# CPU_LPC1776_2.net
KiCad netlist of a schematic drawn in Altium Designer
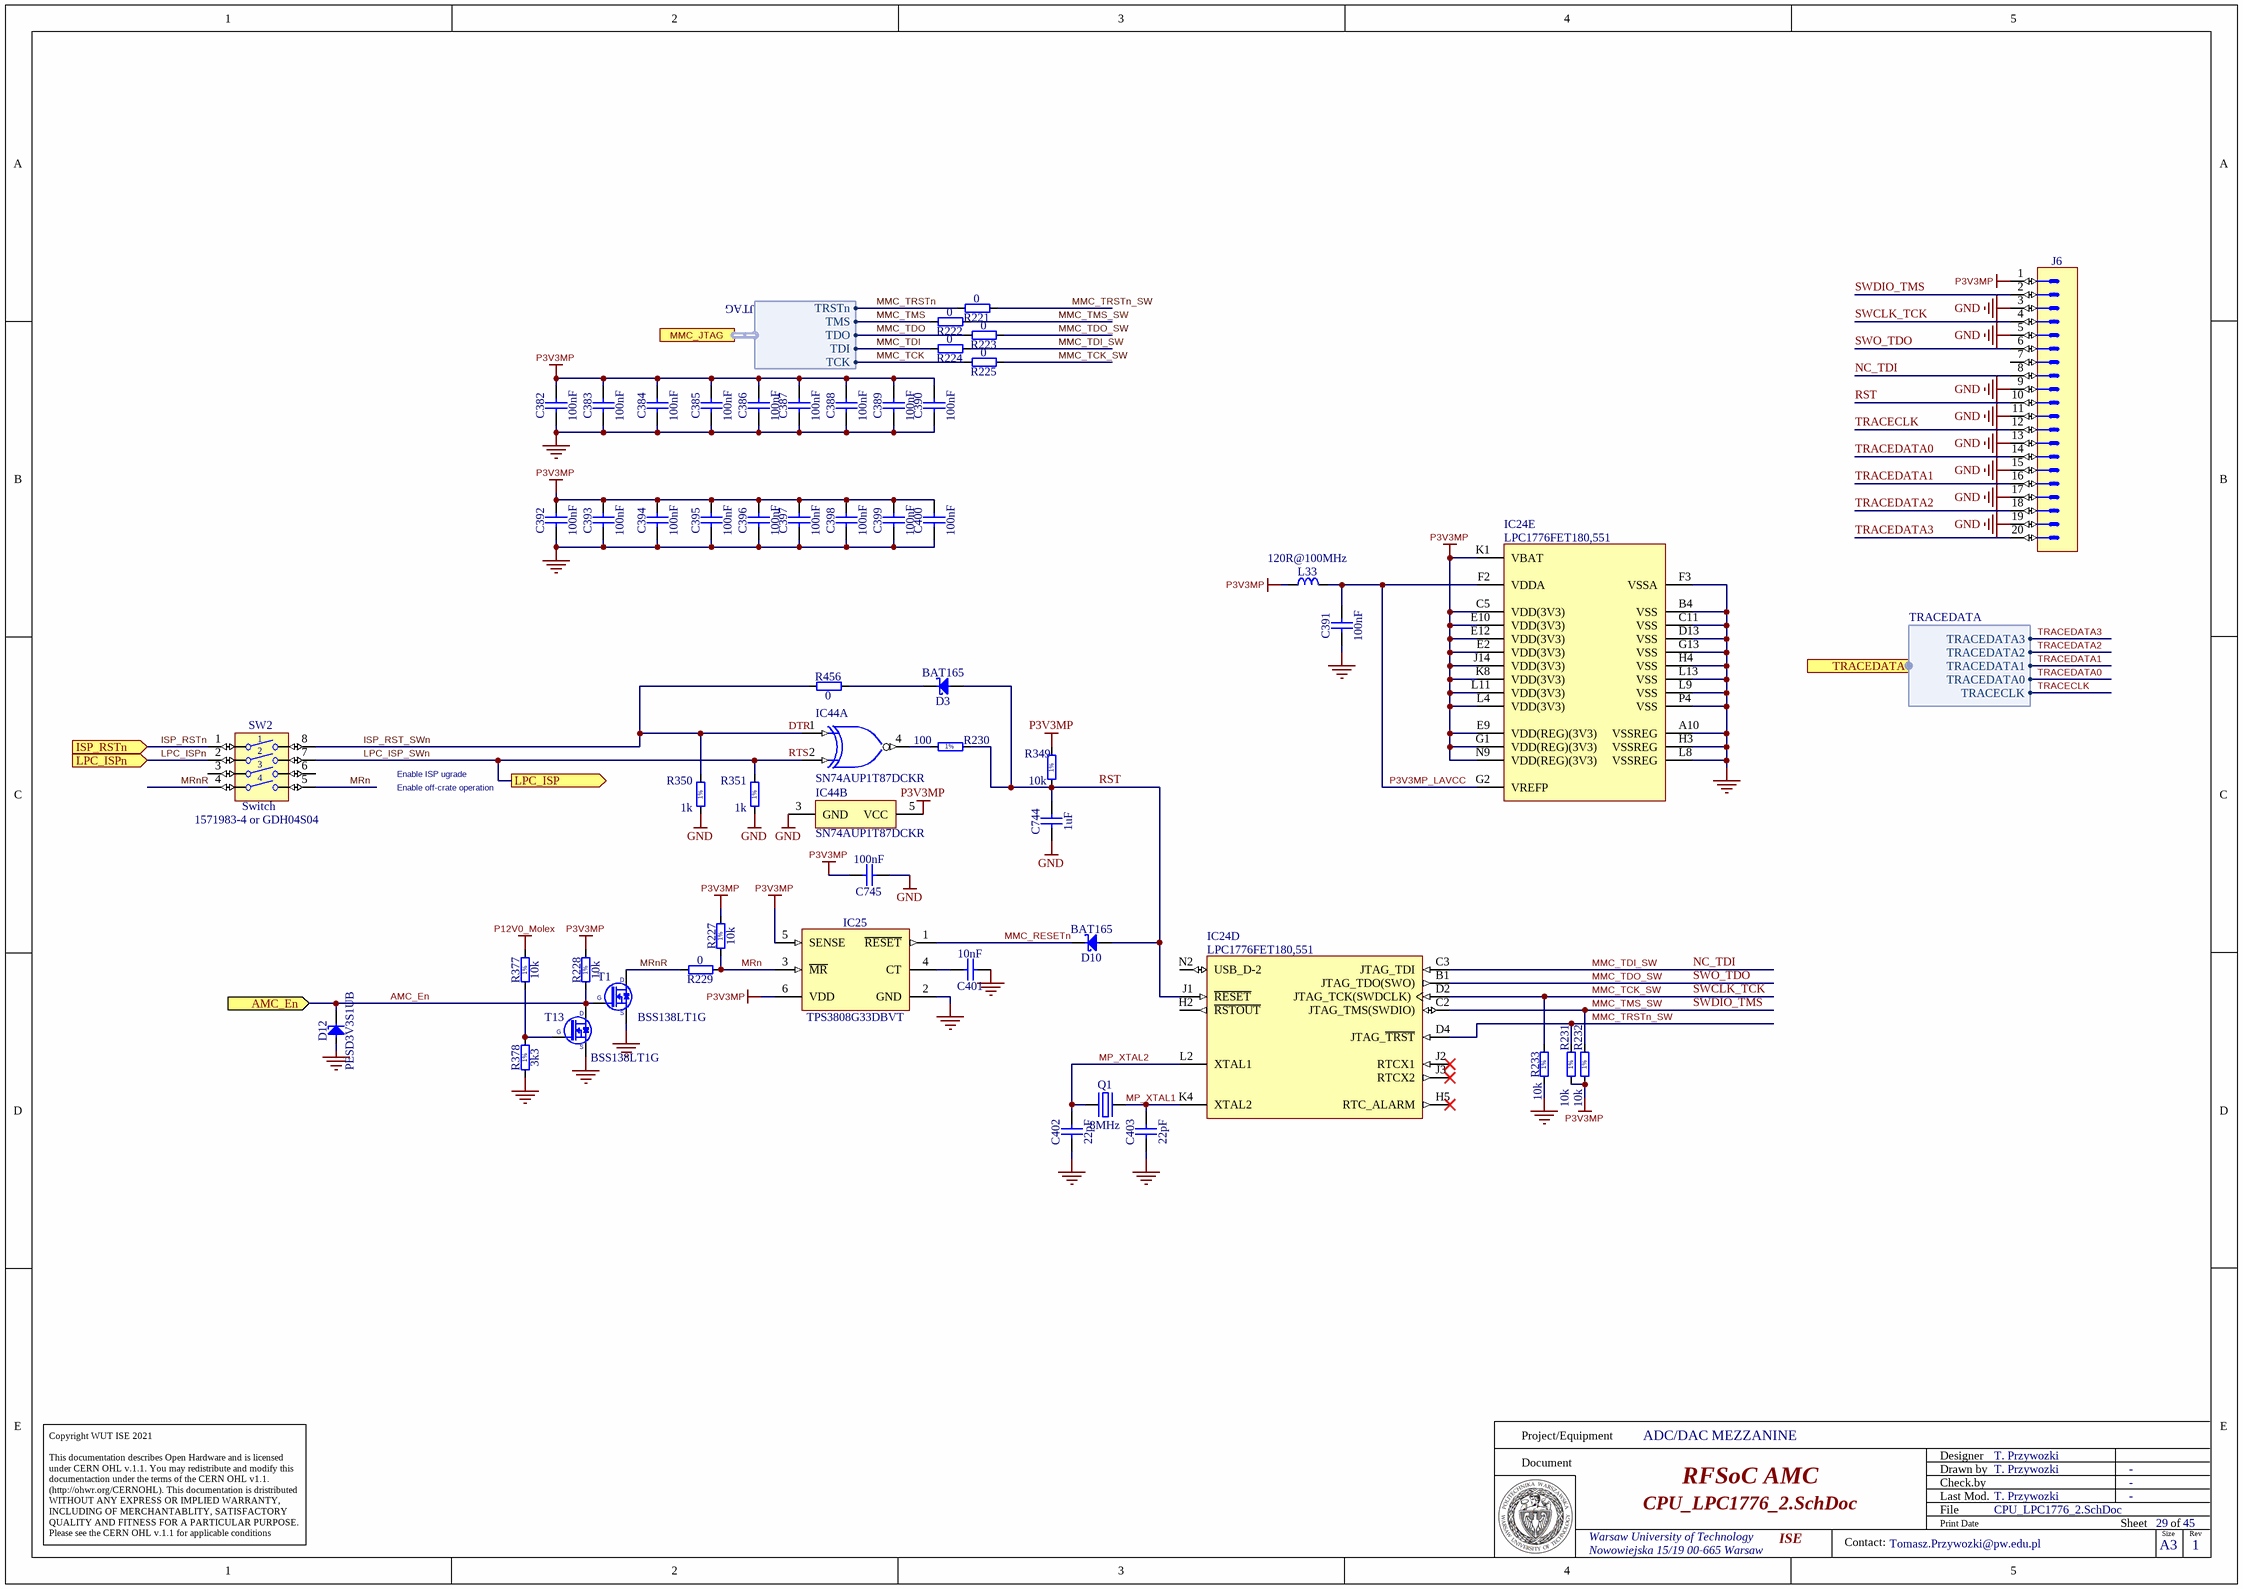
[diagram p0: CPU_LPC1776_2.SchDoc]

(export (version "E")
  (design (tool "Eeschema 10.0.6"))
  (components
    (comp (ref "C382")
      (value "100nF")
      (footprint "CAPC0603X33N")
      (description "Non-polarised capacitor")
      (fields
        (field (name "MANUFACTURER PART NUMBER") "CC0201_100NF_6.3V_10%_X5R")
        (field (name "MANUFACTURER") "GENERIC")
        (field (name "AUTHOR") "CERN DEM JLC")
      )
      (libsource (lib "Capacitors") (part "Capacitor - non polarized"))
    )
    (comp (ref "C383")
      (value "100nF")
      (footprint "CAPC0603X33N")
      (description "Non-polarised capacitor")
      (fields
        (field (name "MANUFACTURER PART NUMBER") "CC0201_100NF_6.3V_10%_X5R")
        (field (name "MANUFACTURER") "GENERIC")
        (field (name "AUTHOR") "CERN DEM JLC")
      )
      (libsource (lib "Capacitors") (part "Capacitor - non polarized"))
    )
    (comp (ref "C384")
      (value "100nF")
      (footprint "CAPC0603X33N")
      (description "Non-polarised capacitor")
      (fields
        (field (name "MANUFACTURER PART NUMBER") "CC0201_100NF_6.3V_10%_X5R")
        (field (name "MANUFACTURER") "GENERIC")
        (field (name "AUTHOR") "CERN DEM JLC")
      )
      (libsource (lib "Capacitors") (part "Capacitor - non polarized"))
    )
    (comp (ref "C385")
      (value "100nF")
      (footprint "CAPC0603X33N")
      (description "Non-polarised capacitor")
      (fields
        (field (name "MANUFACTURER PART NUMBER") "CC0201_100NF_6.3V_10%_X5R")
        (field (name "MANUFACTURER") "GENERIC")
        (field (name "AUTHOR") "CERN DEM JLC")
      )
      (libsource (lib "Capacitors") (part "Capacitor - non polarized"))
    )
    (comp (ref "C386")
      (value "100nF")
      (footprint "CAPC0603X33N")
      (description "Non-polarised capacitor")
      (fields
        (field (name "MANUFACTURER PART NUMBER") "CC0201_100NF_6.3V_10%_X5R")
        (field (name "MANUFACTURER") "GENERIC")
        (field (name "AUTHOR") "CERN DEM JLC")
      )
      (libsource (lib "Capacitors") (part "Capacitor - non polarized"))
    )
    (comp (ref "C387")
      (value "100nF")
      (footprint "CAPC0603X33N")
      (description "Non-polarised capacitor")
      (fields
        (field (name "MANUFACTURER PART NUMBER") "CC0201_100NF_6.3V_10%_X5R")
        (field (name "MANUFACTURER") "GENERIC")
        (field (name "AUTHOR") "CERN DEM JLC")
      )
      (libsource (lib "Capacitors") (part "Capacitor - non polarized"))
    )
    (comp (ref "C388")
      (value "100nF")
      (footprint "CAPC0603X33N")
      (description "Non-polarised capacitor")
      (fields
        (field (name "MANUFACTURER PART NUMBER") "CC0201_100NF_6.3V_10%_X5R")
        (field (name "MANUFACTURER") "GENERIC")
        (field (name "AUTHOR") "CERN DEM JLC")
      )
      (libsource (lib "Capacitors") (part "Capacitor - non polarized"))
    )
    (comp (ref "C389")
      (value "100nF")
      (footprint "CAPC0603X33N")
      (description "Non-polarised capacitor")
      (fields
        (field (name "MANUFACTURER PART NUMBER") "CC0201_100NF_6.3V_10%_X5R")
        (field (name "MANUFACTURER") "GENERIC")
        (field (name "AUTHOR") "CERN DEM JLC")
      )
      (libsource (lib "Capacitors") (part "Capacitor - non polarized"))
    )
    (comp (ref "C390")
      (value "100nF")
      (footprint "CAPC0603X33N")
      (description "Non-polarised capacitor")
      (fields
        (field (name "MANUFACTURER PART NUMBER") "CC0201_100NF_6.3V_10%_X5R")
        (field (name "MANUFACTURER") "GENERIC")
        (field (name "AUTHOR") "CERN DEM JLC")
      )
      (libsource (lib "Capacitors") (part "Capacitor - non polarized"))
    )
    (comp (ref "C391")
      (value "100nF")
      (footprint "CAPC0603X33N")
      (description "Non-polarised capacitor")
      (fields
        (field (name "MANUFACTURER PART NUMBER") "CC0201_100NF_6.3V_10%_X5R")
        (field (name "MANUFACTURER") "GENERIC")
        (field (name "AUTHOR") "CERN DEM JLC")
      )
      (libsource (lib "Capacitors") (part "Capacitor - non polarized"))
    )
    (comp (ref "C392")
      (value "100nF")
      (footprint "CAPC0603X33N")
      (description "Non-polarised capacitor")
      (fields
        (field (name "MANUFACTURER PART NUMBER") "CC0201_100NF_6.3V_10%_X5R")
        (field (name "MANUFACTURER") "GENERIC")
        (field (name "AUTHOR") "CERN DEM JLC")
      )
      (libsource (lib "Capacitors") (part "Capacitor - non polarized"))
    )
    (comp (ref "C393")
      (value "100nF")
      (footprint "CAPC0603X33N")
      (description "Non-polarised capacitor")
      (fields
        (field (name "MANUFACTURER PART NUMBER") "CC0201_100NF_6.3V_10%_X5R")
        (field (name "MANUFACTURER") "GENERIC")
        (field (name "AUTHOR") "CERN DEM JLC")
      )
      (libsource (lib "Capacitors") (part "Capacitor - non polarized"))
    )
    (comp (ref "C394")
      (value "100nF")
      (footprint "CAPC0603X33N")
      (description "Non-polarised capacitor")
      (fields
        (field (name "MANUFACTURER PART NUMBER") "CC0201_100NF_6.3V_10%_X5R")
        (field (name "MANUFACTURER") "GENERIC")
        (field (name "AUTHOR") "CERN DEM JLC")
      )
      (libsource (lib "Capacitors") (part "Capacitor - non polarized"))
    )
    (comp (ref "C395")
      (value "100nF")
      (footprint "CAPC0603X33N")
      (description "Non-polarised capacitor")
      (fields
        (field (name "MANUFACTURER PART NUMBER") "CC0201_100NF_6.3V_10%_X5R")
        (field (name "MANUFACTURER") "GENERIC")
        (field (name "AUTHOR") "CERN DEM JLC")
      )
      (libsource (lib "Capacitors") (part "Capacitor - non polarized"))
    )
    (comp (ref "C396")
      (value "100nF")
      (footprint "CAPC0603X33N")
      (description "Non-polarised capacitor")
      (fields
        (field (name "MANUFACTURER PART NUMBER") "CC0201_100NF_6.3V_10%_X5R")
        (field (name "MANUFACTURER") "GENERIC")
        (field (name "AUTHOR") "CERN DEM JLC")
      )
      (libsource (lib "Capacitors") (part "Capacitor - non polarized"))
    )
    (comp (ref "C397")
      (value "100nF")
      (footprint "CAPC0603X33N")
      (description "Non-polarised capacitor")
      (fields
        (field (name "MANUFACTURER PART NUMBER") "CC0201_100NF_6.3V_10%_X5R")
        (field (name "MANUFACTURER") "GENERIC")
        (field (name "AUTHOR") "CERN DEM JLC")
      )
      (libsource (lib "Capacitors") (part "Capacitor - non polarized"))
    )
    (comp (ref "C398")
      (value "100nF")
      (footprint "CAPC0603X33N")
      (description "Non-polarised capacitor")
      (fields
        (field (name "MANUFACTURER PART NUMBER") "CC0201_100NF_6.3V_10%_X5R")
        (field (name "MANUFACTURER") "GENERIC")
        (field (name "AUTHOR") "CERN DEM JLC")
      )
      (libsource (lib "Capacitors") (part "Capacitor - non polarized"))
    )
    (comp (ref "C399")
      (value "100nF")
      (footprint "CAPC0603X33N")
      (description "Non-polarised capacitor")
      (fields
        (field (name "MANUFACTURER PART NUMBER") "CC0201_100NF_6.3V_10%_X5R")
        (field (name "MANUFACTURER") "GENERIC")
        (field (name "AUTHOR") "CERN DEM JLC")
      )
      (libsource (lib "Capacitors") (part "Capacitor - non polarized"))
    )
    (comp (ref "C400")
      (value "100nF")
      (footprint "CAPC0603X33N")
      (description "Non-polarised capacitor")
      (fields
        (field (name "MANUFACTURER PART NUMBER") "CC0201_100NF_6.3V_10%_X5R")
        (field (name "MANUFACTURER") "GENERIC")
        (field (name "AUTHOR") "CERN DEM JLC")
      )
      (libsource (lib "Capacitors") (part "Capacitor - non polarized"))
    )
    (comp (ref "C401")
      (value "10nF")
      (footprint "CAPC1005X55N")
      (description "Non-polarised capacitor")
      (fields
        (field (name "MANUFACTURER PART NUMBER") "CC0402_10NF_16V_10%_X7R")
        (field (name "MANUFACTURER") "GENERIC")
        (field (name "AUTHOR") "CERN DEM JLC")
      )
      (libsource (lib "Capacitors") (part "Capacitor - non polarized"))
    )
    (comp (ref "C402")
      (value "22pF")
      (footprint "CAPC1005X55N")
      (description "Non-polarised capacitor")
      (fields
        (field (name "MANUFACTURER PART NUMBER") "CC0402_22PF_50V_5%_C0G")
        (field (name "MANUFACTURER") "GENERIC")
        (field (name "AUTHOR") "CERN DEM JLC")
      )
      (libsource (lib "Capacitors") (part "Capacitor - non polarized"))
    )
    (comp (ref "C403")
      (value "22pF")
      (footprint "CAPC1005X55N")
      (description "Non-polarised capacitor")
      (fields
        (field (name "MANUFACTURER PART NUMBER") "CC0402_22PF_50V_5%_C0G")
        (field (name "MANUFACTURER") "GENERIC")
        (field (name "AUTHOR") "CERN DEM JLC")
      )
      (libsource (lib "Capacitors") (part "Capacitor - non polarized"))
    )
    (comp (ref "C744")
      (value "1uF")
      (footprint "CAPC1608X87N")
      (description "Non-polarised capacitor")
      (fields
        (field (name "PART NUMBER") "CC0603_1UF_16V_10%_X7R")
        (field (name "VOLTAGE") "16V")
        (field (name "AUTHOR") "CERN DEM JLC")
      )
      (libsource (lib "Capacitors") (part "Capacitor - non polarized"))
    )
    (comp (ref "C745")
      (value "100nF")
      (footprint "CAPC0603X33N")
      (description "Non-polarised capacitor")
      (fields
        (field (name "PART NUMBER") "CC0201_100NF_6.3V_10%_X5R")
        (field (name "VOLTAGE") "6.3V")
        (field (name "AUTHOR") "CERN DEM JLC")
      )
      (libsource (lib "Capacitors") (part "Capacitor - non polarized"))
    )
    (comp (ref "D3")
      (value "BAT165")
      (footprint "SOD2512X110N")
      (description "Schottky Diode")
      (fields
        (field (name "MANUFACTURER") "INFINEON")
        (field (name "VOLTAGE") "40V")
        (field (name "AUTHOR") "CERN DEM JLC")
      )
      (libsource (lib "ICs And Semiconductors") (part "Diode Schottky"))
    )
    (comp (ref "D10")
      (value "BAT165")
      (footprint "SOD2512X110N")
      (description "Schottky Diode")
      (fields
        (field (name "MANUFACTURER") "INFINEON")
        (field (name "VOLTAGE") "40V")
        (field (name "AUTHOR") "CERN DEM JLC")
      )
      (libsource (lib "ICs And Semiconductors") (part "Diode Schottky"))
    )
    (comp (ref "D12")
      (value "PESD3V3S1UB")
      (footprint "SODFL1608X65N")
      (description "ESD protection diode")
      (fields
        (field (name "MANUFACTURER") "NXP SEMICONDUCTORS")
        (field (name "VOLTAGE") "3V3")
        (field (name "AUTHOR") "CERN DEM JLC")
      )
      (libsource (lib "ICs And Semiconductors") (part "Diode ESD"))
    )
    (comp (ref "IC24")
      (value "LPC1776FET180,551")
      (footprint "BGA180C80P14X14_1200X1200X120")
      (fields (field (name "MANUFACTURER") "NXP SEMICONDUCTORS") (field (name "AUTHOR") "CERN DEM JMW"))
      (libsource (lib "ICs And Semiconductors") (part "LPC1776FET180,551"))
    )
    (comp (ref "IC25")
      (value "TPS3808G33DBVT")
      (footprint "SOT95P280X145-6N")
      (description "Low Quiescent Current, Programmable-Delay Supervisory Circuit")
      (fields (field (name "MANUFACTURER") "TEXAS INSTRUMENTS") (field (name "AUTHOR") "CERN DEM JLC"))
      (libsource (lib "ICs And Semiconductors") (part "TPS3808xxxDBV"))
    )
    (comp (ref "IC44")
      (value "SN74AUP1T87DCKR")
      (footprint "DCK0005A_L")
      (fields
        (field (name "GENERIC PART NUMBER") "SN74AUP1T87")
        (field (name "MANUFACTURER") "Texas Instruments")
      )
      (libsource (lib "") (part "TI-SN74AUP1T87-DCK0005A-5_1"))
    )
    (comp (ref "J6")
      (value "Header 20")
      (footprint "SAMTEC_FTSH-110-01-F-DV-K")
      (description "Connector 20 Male")
      (fields
        (field (name "PART NUMBER") "SAMTEC_FTSH-110-01-F-DV-K")
        (field (name "MANUFACTURER") "SAMTEC")
        (field (name "AUTHOR") "CERN DEM JLC")
      )
      (libsource (lib "Connectors") (part "Connector 20 Male"))
    )
    (comp (ref "L33")
      (value "120R@100MHz")
      (footprint "INDC1608X95N")
      (description "Inductor")
      (fields
        (field (name "MANUFACTURER PART NUMBER") "BLM18PG121SN1D")
        (field (name "MANUFACTURER") "MURATA")
        (field (name "AUTHOR") "CERN DEM BC")
      )
      (libsource (lib "Inductors & Transformers") (part "Inductor"))
    )
    (comp (ref "Q1")
      (value "8MHz")
      (footprint "XTAL_TXC_7A")
      (description "Quartz Crystal")
      (fields
        (field (name "MANUFACTURER PART NUMBER") "7A-8.000MAAE-T")
        (field (name "MANUFACTURER") "TXC CORPORATION")
        (field (name "AUTHOR") "CERN DEM JLC")
      )
      (libsource (lib "ICs And Semiconductors") (part "Quartz Crystal"))
    )
    (comp (ref "R221")
      (value "0")
      (footprint "RESC1005X40N")
      (description "Resistor")
      (fields
        (field (name "MANUFACTURER PART NUMBER") "R0402_0R_JUMPER")
        (field (name "MANUFACTURER") "GENERIC")
        (field (name "AUTHOR") "CERN DEM JLC")
      )
      (libsource (lib "Resistors") (part "Resistor"))
    )
    (comp (ref "R222")
      (value "0")
      (footprint "RESC1005X40N")
      (description "Resistor")
      (fields
        (field (name "MANUFACTURER PART NUMBER") "R0402_0R_JUMPER")
        (field (name "MANUFACTURER") "GENERIC")
        (field (name "AUTHOR") "CERN DEM JLC")
      )
      (libsource (lib "Resistors") (part "Resistor"))
    )
    (comp (ref "R223")
      (value "0")
      (footprint "RESC1005X40N")
      (description "Resistor")
      (fields
        (field (name "MANUFACTURER PART NUMBER") "R0402_0R_JUMPER")
        (field (name "MANUFACTURER") "GENERIC")
        (field (name "AUTHOR") "CERN DEM JLC")
      )
      (libsource (lib "Resistors") (part "Resistor"))
    )
    (comp (ref "R224")
      (value "0")
      (footprint "RESC1005X40N")
      (description "Resistor")
      (fields
        (field (name "MANUFACTURER PART NUMBER") "R0402_0R_JUMPER")
        (field (name "MANUFACTURER") "GENERIC")
        (field (name "AUTHOR") "CERN DEM JLC")
      )
      (libsource (lib "Resistors") (part "Resistor"))
    )
    (comp (ref "R225")
      (value "0")
      (footprint "RESC1005X40N")
      (description "Resistor")
      (fields
        (field (name "MANUFACTURER PART NUMBER") "R0402_0R_JUMPER")
        (field (name "MANUFACTURER") "GENERIC")
        (field (name "AUTHOR") "CERN DEM JLC")
      )
      (libsource (lib "Resistors") (part "Resistor"))
    )
    (comp (ref "R227")
      (value "10k")
      (footprint "RESC1005X40N")
      (description "Resistor - 1%")
      (fields
        (field (name "MANUFACTURER PART NUMBER") "R0402_10K_1%_0.0625W_100PPM")
        (field (name "MANUFACTURER") "GENERIC")
        (field (name "AUTHOR") "CERN DEM JLC")
      )
      (libsource (lib "Resistors") (part "Resistor - 1%"))
    )
    (comp (ref "R228")
      (value "10k")
      (footprint "RESC1005X40N")
      (description "Resistor - 1%")
      (fields
        (field (name "MANUFACTURER PART NUMBER") "R0402_10K_1%_0.0625W_100PPM")
        (field (name "MANUFACTURER") "GENERIC")
        (field (name "AUTHOR") "CERN DEM JLC")
      )
      (libsource (lib "Resistors") (part "Resistor - 1%"))
    )
    (comp (ref "R229")
      (value "0")
      (footprint "RESC1005X40N")
      (description "Resistor")
      (fields
        (field (name "MANUFACTURER PART NUMBER") "R0402_0R_JUMPER")
        (field (name "MANUFACTURER") "GENERIC")
        (field (name "AUTHOR") "CERN DEM JLC")
      )
      (libsource (lib "Resistors") (part "Resistor"))
    )
    (comp (ref "R230")
      (value "100")
      (footprint "RESC1005X40N")
      (description "Resistor - 1%")
      (fields
        (field (name "MANUFACTURER PART NUMBER") "R0402_100R_1%_0.1W_100PPM_50V")
        (field (name "MANUFACTURER") "GENERIC")
        (field (name "AUTHOR") "CERN DEM JLC")
      )
      (libsource (lib "Resistors") (part "Resistor - 1%"))
    )
    (comp (ref "R231")
      (value "10k")
      (footprint "RESC1005X40N")
      (description "Resistor - 1%")
      (fields
        (field (name "MANUFACTURER PART NUMBER") "R0402_10K_1%_0.0625W_100PPM")
        (field (name "MANUFACTURER") "GENERIC")
        (field (name "AUTHOR") "CERN DEM JLC")
      )
      (libsource (lib "Resistors") (part "Resistor - 1%"))
    )
    (comp (ref "R232")
      (value "10k")
      (footprint "RESC1005X40N")
      (description "Resistor - 1%")
      (fields
        (field (name "MANUFACTURER PART NUMBER") "R0402_10K_1%_0.0625W_100PPM")
        (field (name "MANUFACTURER") "GENERIC")
        (field (name "AUTHOR") "CERN DEM JLC")
      )
      (libsource (lib "Resistors") (part "Resistor - 1%"))
    )
    (comp (ref "R233")
      (value "10k")
      (footprint "RESC1005X40N")
      (description "Resistor - 1%")
      (fields
        (field (name "MANUFACTURER PART NUMBER") "R0402_10K_1%_0.0625W_100PPM")
        (field (name "MANUFACTURER") "GENERIC")
        (field (name "AUTHOR") "CERN DEM JLC")
      )
      (libsource (lib "Resistors") (part "Resistor - 1%"))
    )
    (comp (ref "R349")
      (value "10k")
      (footprint "RESC1005X40N")
      (description "Resistor - 1%")
      (fields
        (field (name "PART NUMBER") "R0402_10K_1%_0.0625W_100PPM")
        (field (name "POWER") "0.0625W")
        (field (name "AUTHOR") "CERN DEM JLC")
      )
      (libsource (lib "Resistors") (part "Resistor - 1%"))
    )
    (comp (ref "R350")
      (value "1k")
      (footprint "RESC1005X40N")
      (description "Resistor - 1%")
      (fields
        (field (name "PART NUMBER") "R0402_1K_1%_0.0625W_100PPM")
        (field (name "POWER") "0.0625W")
        (field (name "AUTHOR") "CERN DEM JLC")
      )
      (libsource (lib "Resistors") (part "Resistor - 1%"))
    )
    (comp (ref "R351")
      (value "1k")
      (footprint "RESC1005X40N")
      (description "Resistor - 1%")
      (fields
        (field (name "PART NUMBER") "R0402_1K_1%_0.0625W_100PPM")
        (field (name "POWER") "0.0625W")
        (field (name "AUTHOR") "CERN DEM JLC")
      )
      (libsource (lib "Resistors") (part "Resistor - 1%"))
    )
    (comp (ref "R377")
      (value "10k")
      (footprint "RESC1005X40N")
      (description "Resistor - 1%")
      (fields
        (field (name "MANUFACTURER PART NUMBER") "R0402_10K_1%_0.0625W_100PPM")
        (field (name "MANUFACTURER") "GENERIC")
        (field (name "AUTHOR") "CERN DEM JLC")
      )
      (libsource (lib "Resistors") (part "Resistor - 1%"))
    )
    (comp (ref "R378")
      (value "3k3")
      (footprint "RESC1608X55N")
      (description "Resistor - 1%")
      (fields
        (field (name "PART NUMBER") "R0603_3K3_1%_0.1W_100PPM")
        (field (name "POWER") "0.1W")
        (field (name "AUTHOR") "CERN DEM JLC")
      )
      (libsource (lib "Resistors") (part "Resistor - 1%"))
    )
    (comp (ref "R456")
      (value "0")
      (footprint "RESC1005X40N")
      (description "Resistor")
      (fields
        (field (name "MANUFACTURER PART NUMBER") "R0402_0R_JUMPER")
        (field (name "MANUFACTURER") "GENERIC")
        (field (name "AUTHOR") "CERN DEM JLC")
      )
      (libsource (lib "Resistors") (part "Resistor"))
    )
    (comp (ref "SW2")
      (value "Switch")
      (footprint "SW_TYCO_1571983-4")
      (description "4 Ways SPST DIP Switch")
      (fields
        (field (name "MANUFACTURER PART NUMBER") "1571983-4 or GDH04S04")
        (field (name "MANUFACTURER") "TYCO")
        (field (name "PART NUMBER") "SW_TYCO_1571983-4")
        (field (name "AUTHOR") "CERN DEM JLC")
      )
      (libsource (lib "Eletro-mechanical") (part "SW 4x SPST DIP Switch"))
    )
    (comp (ref "T1")
      (value "BSS138LT1G")
      (footprint "SOT95P240X110-3N")
      (description "N-CHANNEL MOSFET WITH DIODE")
      (fields (field (name "MANUFACTURER") "ON SEMICONDUCTOR") (field (name "AUTHOR") "CERN DEM JLC"))
      (libsource (lib "ICs And Semiconductors") (part "N-MOSFET-D 1G 2S 3D"))
    )
    (comp (ref "T13")
      (value "BSS138LT1G")
      (footprint "SOT95P240X110-3N")
      (description "N-CHANNEL MOSFET WITH DIODE")
      (fields (field (name "MANUFACTURER") "ON SEMICONDUCTOR") (field (name "AUTHOR") "CERN DEM JLC"))
      (libsource (lib "ICs And Semiconductors") (part "N-MOSFET-D 1G 2S 3D"))
    )
  )
  (nets
    (net (code "3") (name "/AMC_En") (class "Default")
      (node (ref "D12") (pin "1") (pinfunction "C_1") (pintype "passive"))
      (node (ref "R228") (pin "1") (pinfunction "1_1") (pintype "passive"))
      (node (ref "T1") (pin "1") (pinfunction "G_1") (pintype "passive"))
      (node (ref "T13") (pin "3") (pinfunction "D_3") (pintype "passive"))
    )
    (net (code "4") (name "/DTR") (class "Default")
      (node (ref "IC44") (pin "1") (pinfunction "A_1") (pintype "input"))
      (node (ref "R350") (pin "2") (pinfunction "2_2") (pintype "passive"))
      (node (ref "R456") (pin "1") (pinfunction "1_1") (pintype "passive"))
      (node (ref "SW2") (pin "8") (pinfunction "8_8") (pintype "bidirectional"))
    )
    (net (code "5") (name "/ISP_RSTn") (class "Default")
      (node (ref "SW2") (pin "1") (pinfunction "1_1") (pintype "bidirectional"))
    )
    (net (code "6") (name "/LPC_ISP_SWn") (class "Default")
      (node (ref "IC44") (pin "2") (pinfunction "B_2") (pintype "input"))
      (node (ref "R351") (pin "2") (pinfunction "2_2") (pintype "passive"))
      (node (ref "SW2") (pin "7") (pinfunction "7_7") (pintype "bidirectional"))
    )
    (net (code "7") (name "/LPC_ISPn") (class "Default")
      (node (ref "SW2") (pin "2") (pinfunction "2_2") (pintype "bidirectional"))
    )
    (net (code "8") (name "/MMC_RESETn") (class "Default")
      (node (ref "D10") (pin "1") (pinfunction "C_1") (pintype "passive"))
      (node (ref "IC25") (pin "1") (pinfunction "~{RESET}_1") (pintype "output"))
    )
    (net (code "9") (name "/MMC_TCK") (class "Default")
      (node (ref "R225") (pin "2") (pinfunction "2_2") (pintype "passive"))
    )
    (net (code "10") (name "/MMC_TCK_SW") (class "Default")
      (node (ref "IC24") (pin "D2") (pinfunction "JTAG_TCK(SWDCLK)_D2") (pintype "input"))
      (node (ref "J6") (pin "4") (pinfunction "4_4") (pintype "bidirectional"))
      (node (ref "R225") (pin "1") (pinfunction "1_1") (pintype "passive"))
      (node (ref "R233") (pin "2") (pinfunction "2_2") (pintype "passive"))
    )
    (net (code "11") (name "/MMC_TDI") (class "Default")
      (node (ref "R224") (pin "2") (pinfunction "2_2") (pintype "passive"))
    )
    (net (code "12") (name "/MMC_TDI_SW") (class "Default")
      (node (ref "IC24") (pin "C3") (pinfunction "JTAG_TDI_C3") (pintype "input"))
      (node (ref "J6") (pin "8") (pinfunction "8_8") (pintype "bidirectional"))
      (node (ref "R224") (pin "1") (pinfunction "1_1") (pintype "passive"))
    )
    (net (code "13") (name "/MMC_TDO") (class "Default")
      (node (ref "R223") (pin "2") (pinfunction "2_2") (pintype "passive"))
    )
    (net (code "14") (name "/MMC_TDO_SW") (class "Default")
      (node (ref "IC24") (pin "B1") (pinfunction "JTAG_TDO(SWO)_B1") (pintype "output"))
      (node (ref "J6") (pin "6") (pinfunction "6_6") (pintype "bidirectional"))
      (node (ref "R223") (pin "1") (pinfunction "1_1") (pintype "passive"))
    )
    (net (code "15") (name "/MMC_TMS") (class "Default")
      (node (ref "R222") (pin "2") (pinfunction "2_2") (pintype "passive"))
    )
    (net (code "16") (name "/MMC_TMS_SW") (class "Default")
      (node (ref "IC24") (pin "C2") (pinfunction "JTAG_TMS(SWDIO)_C2") (pintype "bidirectional"))
      (node (ref "J6") (pin "2") (pinfunction "2_2") (pintype "bidirectional"))
      (node (ref "R222") (pin "1") (pinfunction "1_1") (pintype "passive"))
      (node (ref "R232") (pin "2") (pinfunction "2_2") (pintype "passive"))
    )
    (net (code "17") (name "/MMC_TRSTn") (class "Default")
      (node (ref "R221") (pin "2") (pinfunction "2_2") (pintype "passive"))
    )
    (net (code "18") (name "/MMC_TRSTn_SW") (class "Default")
      (node (ref "IC24") (pin "D4") (pinfunction "JTAG_~{TRST}_D4") (pintype "input"))
      (node (ref "R221") (pin "1") (pinfunction "1_1") (pintype "passive"))
      (node (ref "R231") (pin "2") (pinfunction "2_2") (pintype "passive"))
    )
    (net (code "19") (name "/MP_XTAL1") (class "Default")
      (node (ref "C403") (pin "2") (pinfunction "2_2") (pintype "passive"))
      (node (ref "IC24") (pin "K4") (pinfunction "XTAL2_K4") (pintype "passive"))
      (node (ref "Q1") (pin "2") (pinfunction "OSC2_2") (pintype "passive"))
    )
    (net (code "20") (name "/MP_XTAL2") (class "Default")
      (node (ref "C402") (pin "2") (pinfunction "2_2") (pintype "passive"))
      (node (ref "IC24") (pin "L2") (pinfunction "XTAL1_L2") (pintype "passive"))
      (node (ref "Q1") (pin "1") (pinfunction "OSC1_1") (pintype "passive"))
    )
    (net (code "21") (name "/MRn") (class "Default")
      (node (ref "IC25") (pin "3") (pinfunction "~{MR}_3") (pintype "input"))
      (node (ref "R227") (pin "1") (pinfunction "1_1") (pintype "passive"))
      (node (ref "R229") (pin "1") (pinfunction "1_1") (pintype "passive"))
      (node (ref "SW2") (pin "5") (pinfunction "5_5") (pintype "bidirectional"))
    )
    (net (code "22") (name "/MRnR") (class "Default")
      (node (ref "R229") (pin "2") (pinfunction "2_2") (pintype "passive"))
      (node (ref "SW2") (pin "4") (pinfunction "4_4") (pintype "bidirectional"))
      (node (ref "T1") (pin "3") (pinfunction "D_3") (pintype "passive"))
    )
    (net (code "23") (name "/P3V3MP_LAVCC") (class "Default")
      (node (ref "C391") (pin "1") (pinfunction "1_1") (pintype "passive"))
      (node (ref "IC24") (pin "F2") (pinfunction "VDDA_F2") (pintype "power_in"))
      (node (ref "IC24") (pin "G2") (pinfunction "VREFP_G2") (pintype "power_in"))
      (node (ref "L33") (pin "1") (pinfunction "1_1") (pintype "passive"))
    )
    (net (code "24") (name "/RST") (class "Default")
      (node (ref "C744") (pin "1") (pinfunction "1_1") (pintype "passive"))
      (node (ref "D10") (pin "2") (pinfunction "A_2") (pintype "passive"))
      (node (ref "D3") (pin "2") (pinfunction "A_2") (pintype "passive"))
      (node (ref "IC24") (pin "J1") (pinfunction "~{RESET}_J1") (pintype "input"))
      (node (ref "J6") (pin "10") (pinfunction "10_10") (pintype "bidirectional"))
      (node (ref "R230") (pin "2") (pinfunction "2_2") (pintype "passive"))
      (node (ref "R349") (pin "1") (pinfunction "1_1") (pintype "passive"))
    )
    (net (code "25") (name "/TRACECLK") (class "Default")
      (node (ref "J6") (pin "12") (pinfunction "12_12") (pintype "bidirectional"))
    )
    (net (code "26") (name "/TRACEDATA0") (class "Default")
      (node (ref "J6") (pin "14") (pinfunction "14_14") (pintype "bidirectional"))
    )
    (net (code "27") (name "/TRACEDATA1") (class "Default")
      (node (ref "J6") (pin "16") (pinfunction "16_16") (pintype "bidirectional"))
    )
    (net (code "28") (name "/TRACEDATA2") (class "Default")
      (node (ref "J6") (pin "18") (pinfunction "18_18") (pintype "bidirectional"))
    )
    (net (code "29") (name "/TRACEDATA3") (class "Default")
      (node (ref "J6") (pin "20") (pinfunction "20_20") (pintype "bidirectional"))
    )
    (net (code "32") (name "GND") (class "Default")
      (node (ref "C382") (pin "2") (pinfunction "2_2") (pintype "passive"))
      (node (ref "C383") (pin "2") (pinfunction "2_2") (pintype "passive"))
      (node (ref "C384") (pin "2") (pinfunction "2_2") (pintype "passive"))
      (node (ref "C385") (pin "2") (pinfunction "2_2") (pintype "passive"))
      (node (ref "C386") (pin "2") (pinfunction "2_2") (pintype "passive"))
      (node (ref "C387") (pin "2") (pinfunction "2_2") (pintype "passive"))
      (node (ref "C388") (pin "2") (pinfunction "2_2") (pintype "passive"))
      (node (ref "C389") (pin "2") (pinfunction "2_2") (pintype "passive"))
      (node (ref "C390") (pin "2") (pinfunction "2_2") (pintype "passive"))
      (node (ref "C391") (pin "2") (pinfunction "2_2") (pintype "passive"))
      (node (ref "C392") (pin "2") (pinfunction "2_2") (pintype "passive"))
      (node (ref "C393") (pin "2") (pinfunction "2_2") (pintype "passive"))
      (node (ref "C394") (pin "2") (pinfunction "2_2") (pintype "passive"))
      (node (ref "C395") (pin "2") (pinfunction "2_2") (pintype "passive"))
      (node (ref "C396") (pin "2") (pinfunction "2_2") (pintype "passive"))
      (node (ref "C397") (pin "2") (pinfunction "2_2") (pintype "passive"))
      (node (ref "C398") (pin "2") (pinfunction "2_2") (pintype "passive"))
      (node (ref "C399") (pin "2") (pinfunction "2_2") (pintype "passive"))
      (node (ref "C400") (pin "2") (pinfunction "2_2") (pintype "passive"))
      (node (ref "C401") (pin "1") (pinfunction "1_1") (pintype "passive"))
      (node (ref "C402") (pin "1") (pinfunction "1_1") (pintype "passive"))
      (node (ref "C403") (pin "1") (pinfunction "1_1") (pintype "passive"))
      (node (ref "C744") (pin "2") (pinfunction "2_2") (pintype "passive"))
      (node (ref "C745") (pin "2") (pinfunction "2_2") (pintype "passive"))
      (node (ref "D12") (pin "2") (pinfunction "A_2") (pintype "passive"))
      (node (ref "IC24") (pin "A10") (pinfunction "VSSREG_A10") (pintype "power_in"))
      (node (ref "IC24") (pin "B4") (pinfunction "VSS_B4") (pintype "power_in"))
      (node (ref "IC24") (pin "C11") (pinfunction "VSS_C11") (pintype "power_in"))
      (node (ref "IC24") (pin "D13") (pinfunction "VSS_D13") (pintype "power_in"))
      (node (ref "IC24") (pin "F3") (pinfunction "VSSA_F3") (pintype "power_in"))
      (node (ref "IC24") (pin "G13") (pinfunction "VSS_G13") (pintype "power_in"))
      (node (ref "IC24") (pin "H3") (pinfunction "VSSREG_H3") (pintype "power_in"))
      (node (ref "IC24") (pin "H4") (pinfunction "VSS_H4") (pintype "power_in"))
      (node (ref "IC24") (pin "L13") (pinfunction "VSS_L13") (pintype "power_in"))
      (node (ref "IC24") (pin "L8") (pinfunction "VSSREG_L8") (pintype "power_in"))
      (node (ref "IC24") (pin "L9") (pinfunction "VSS_L9") (pintype "power_in"))
      (node (ref "IC24") (pin "P4") (pinfunction "VSS_P4") (pintype "power_in"))
      (node (ref "IC25") (pin "2") (pinfunction "GND_2") (pintype "power_in"))
      (node (ref "IC44") (pin "3") (pinfunction "GND_3") (pintype "power_in"))
      (node (ref "J6") (pin "11") (pinfunction "11_11") (pintype "bidirectional"))
      (node (ref "J6") (pin "13") (pinfunction "13_13") (pintype "bidirectional"))
      (node (ref "J6") (pin "15") (pinfunction "15_15") (pintype "bidirectional"))
      (node (ref "J6") (pin "17") (pinfunction "17_17") (pintype "bidirectional"))
      (node (ref "J6") (pin "19") (pinfunction "19_19") (pintype "bidirectional"))
      (node (ref "J6") (pin "3") (pinfunction "3_3") (pintype "bidirectional"))
      (node (ref "J6") (pin "5") (pinfunction "5_5") (pintype "bidirectional"))
      (node (ref "J6") (pin "9") (pinfunction "9_9") (pintype "bidirectional"))
      (node (ref "R233") (pin "1") (pinfunction "1_1") (pintype "passive"))
      (node (ref "R350") (pin "1") (pinfunction "1_1") (pintype "passive"))
      (node (ref "R351") (pin "1") (pinfunction "1_1") (pintype "passive"))
      (node (ref "R378") (pin "1") (pinfunction "1_1") (pintype "passive"))
      (node (ref "T1") (pin "2") (pinfunction "S_2") (pintype "passive"))
      (node (ref "T13") (pin "2") (pinfunction "S_2") (pintype "passive"))
    )
    (net (code "33") (name "Net-(D3-C)") (class "Default")
      (node (ref "D3") (pin "1") (pinfunction "C_1") (pintype "passive"))
      (node (ref "R456") (pin "2") (pinfunction "2_2") (pintype "passive"))
    )
    (net (code "34") (name "Net-(IC25-CT)") (class "Default")
      (node (ref "C401") (pin "2") (pinfunction "2_2") (pintype "passive"))
      (node (ref "IC25") (pin "4") (pinfunction "CT_4") (pintype "passive"))
    )
    (net (code "35") (name "Net-(IC44A-Y)") (class "Default")
      (node (ref "IC44") (pin "4") (pinfunction "Y_4") (pintype "output"))
      (node (ref "R230") (pin "1") (pinfunction "1_1") (pintype "passive"))
    )
    (net (code "36") (name "Net-(T13-G)") (class "Default")
      (node (ref "R377") (pin "1") (pinfunction "1_1") (pintype "passive"))
      (node (ref "R378") (pin "2") (pinfunction "2_2") (pintype "passive"))
      (node (ref "T13") (pin "1") (pinfunction "G_1") (pintype "passive"))
    )
    (net (code "37") (name "P3V3MP") (class "Default")
      (node (ref "C382") (pin "1") (pinfunction "1_1") (pintype "passive"))
      (node (ref "C383") (pin "1") (pinfunction "1_1") (pintype "passive"))
      (node (ref "C384") (pin "1") (pinfunction "1_1") (pintype "passive"))
      (node (ref "C385") (pin "1") (pinfunction "1_1") (pintype "passive"))
      (node (ref "C386") (pin "1") (pinfunction "1_1") (pintype "passive"))
      (node (ref "C387") (pin "1") (pinfunction "1_1") (pintype "passive"))
      (node (ref "C388") (pin "1") (pinfunction "1_1") (pintype "passive"))
      (node (ref "C389") (pin "1") (pinfunction "1_1") (pintype "passive"))
      (node (ref "C390") (pin "1") (pinfunction "1_1") (pintype "passive"))
      (node (ref "C392") (pin "1") (pinfunction "1_1") (pintype "passive"))
      (node (ref "C393") (pin "1") (pinfunction "1_1") (pintype "passive"))
      (node (ref "C394") (pin "1") (pinfunction "1_1") (pintype "passive"))
      (node (ref "C395") (pin "1") (pinfunction "1_1") (pintype "passive"))
      (node (ref "C396") (pin "1") (pinfunction "1_1") (pintype "passive"))
      (node (ref "C397") (pin "1") (pinfunction "1_1") (pintype "passive"))
      (node (ref "C398") (pin "1") (pinfunction "1_1") (pintype "passive"))
      (node (ref "C399") (pin "1") (pinfunction "1_1") (pintype "passive"))
      (node (ref "C400") (pin "1") (pinfunction "1_1") (pintype "passive"))
      (node (ref "C745") (pin "1") (pinfunction "1_1") (pintype "passive"))
      (node (ref "IC24") (pin "C5") (pinfunction "VDD(3V3)_C5") (pintype "power_in"))
      (node (ref "IC24") (pin "E10") (pinfunction "VDD(3V3)_E10") (pintype "power_in"))
      (node (ref "IC24") (pin "E12") (pinfunction "VDD(3V3)_E12") (pintype "power_in"))
      (node (ref "IC24") (pin "E2") (pinfunction "VDD(3V3)_E2") (pintype "power_in"))
      (node (ref "IC24") (pin "E9") (pinfunction "VDD(REG)(3V3)_E9") (pintype "power_in"))
      (node (ref "IC24") (pin "G1") (pinfunction "VDD(REG)(3V3)_G1") (pintype "power_in"))
      (node (ref "IC24") (pin "J14") (pinfunction "VDD(3V3)_J14") (pintype "power_in"))
      (node (ref "IC24") (pin "K1") (pinfunction "VBAT_K1") (pintype "power_in"))
      (node (ref "IC24") (pin "K8") (pinfunction "VDD(3V3)_K8") (pintype "power_in"))
      (node (ref "IC24") (pin "L11") (pinfunction "VDD(3V3)_L11") (pintype "power_in"))
      (node (ref "IC24") (pin "L4") (pinfunction "VDD(3V3)_L4") (pintype "power_in"))
      (node (ref "IC24") (pin "N9") (pinfunction "VDD(REG)(3V3)_N9") (pintype "power_in"))
      (node (ref "IC25") (pin "5") (pinfunction "SENSE_5") (pintype "input"))
      (node (ref "IC25") (pin "6") (pinfunction "VDD_6") (pintype "power_in"))
      (node (ref "IC44") (pin "5") (pinfunction "VCC_5") (pintype "power_in"))
      (node (ref "J6") (pin "1") (pinfunction "1_1") (pintype "bidirectional"))
      (node (ref "L33") (pin "2") (pinfunction "2_2") (pintype "passive"))
      (node (ref "R227") (pin "2") (pinfunction "2_2") (pintype "passive"))
      (node (ref "R228") (pin "2") (pinfunction "2_2") (pintype "passive"))
      (node (ref "R231") (pin "1") (pinfunction "1_1") (pintype "passive"))
      (node (ref "R232") (pin "1") (pinfunction "1_1") (pintype "passive"))
      (node (ref "R349") (pin "2") (pinfunction "2_2") (pintype "passive"))
    )
    (net (code "38") (name "P12V0_Molex") (class "Default")
      (node (ref "R377") (pin "2") (pinfunction "2_2") (pintype "passive"))
    )
    (net (code "39") (name "unconnected-(IC24D-RTCX1-PadJ2)") (class "Default")
      (node (ref "IC24") (pin "J2") (pinfunction "RTCX1_J2") (pintype "input+no_connect"))
    )
    (net (code "40") (name "unconnected-(IC24D-RTCX2-PadJ3)") (class "Default")
      (node (ref "IC24") (pin "J3") (pinfunction "RTCX2_J3") (pintype "output+no_connect"))
    )
    (net (code "41") (name "unconnected-(IC24D-RTC_ALARM-PadH5)") (class "Default")
      (node (ref "IC24") (pin "H5") (pinfunction "RTC_ALARM_H5") (pintype "output+no_connect"))
    )
    (net (code "42") (name "unconnected-(IC24D-USB_D-2-PadN2)") (class "Default")
      (node (ref "IC24") (pin "N2") (pinfunction "USB_D-2_N2") (pintype "bidirectional"))
    )
    (net (code "43") (name "unconnected-(IC24D-~{RSTOUT}-PadH2)") (class "Default")
      (node (ref "IC24") (pin "H2") (pinfunction "~{RSTOUT}_H2") (pintype "output"))
    )
    (net (code "44") (name "unconnected-(J6-Pad7)") (class "Default")
      (node (ref "J6") (pin "7") (pinfunction "7_7") (pintype "bidirectional"))
    )
    (net (code "45") (name "unconnected-(SW2-Pad3)") (class "Default")
      (node (ref "SW2") (pin "3") (pinfunction "3_3") (pintype "bidirectional"))
    )
    (net (code "46") (name "unconnected-(SW2-Pad6)") (class "Default")
      (node (ref "SW2") (pin "6") (pinfunction "6_6") (pintype "bidirectional"))
    )
  )
)
